# MotionControllerV1_1_EtherCAT.net
KiCad netlist of a schematic drawn in Altium Designer
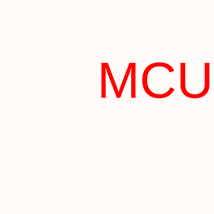
[diagram p0: MotionControllerV1.1_EtherCAT.SchDoc, top left]
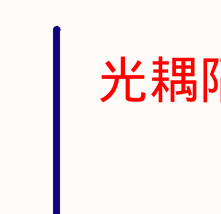
[diagram p1: MotionControllerV1.1_EtherCAT.SchDoc, top right]
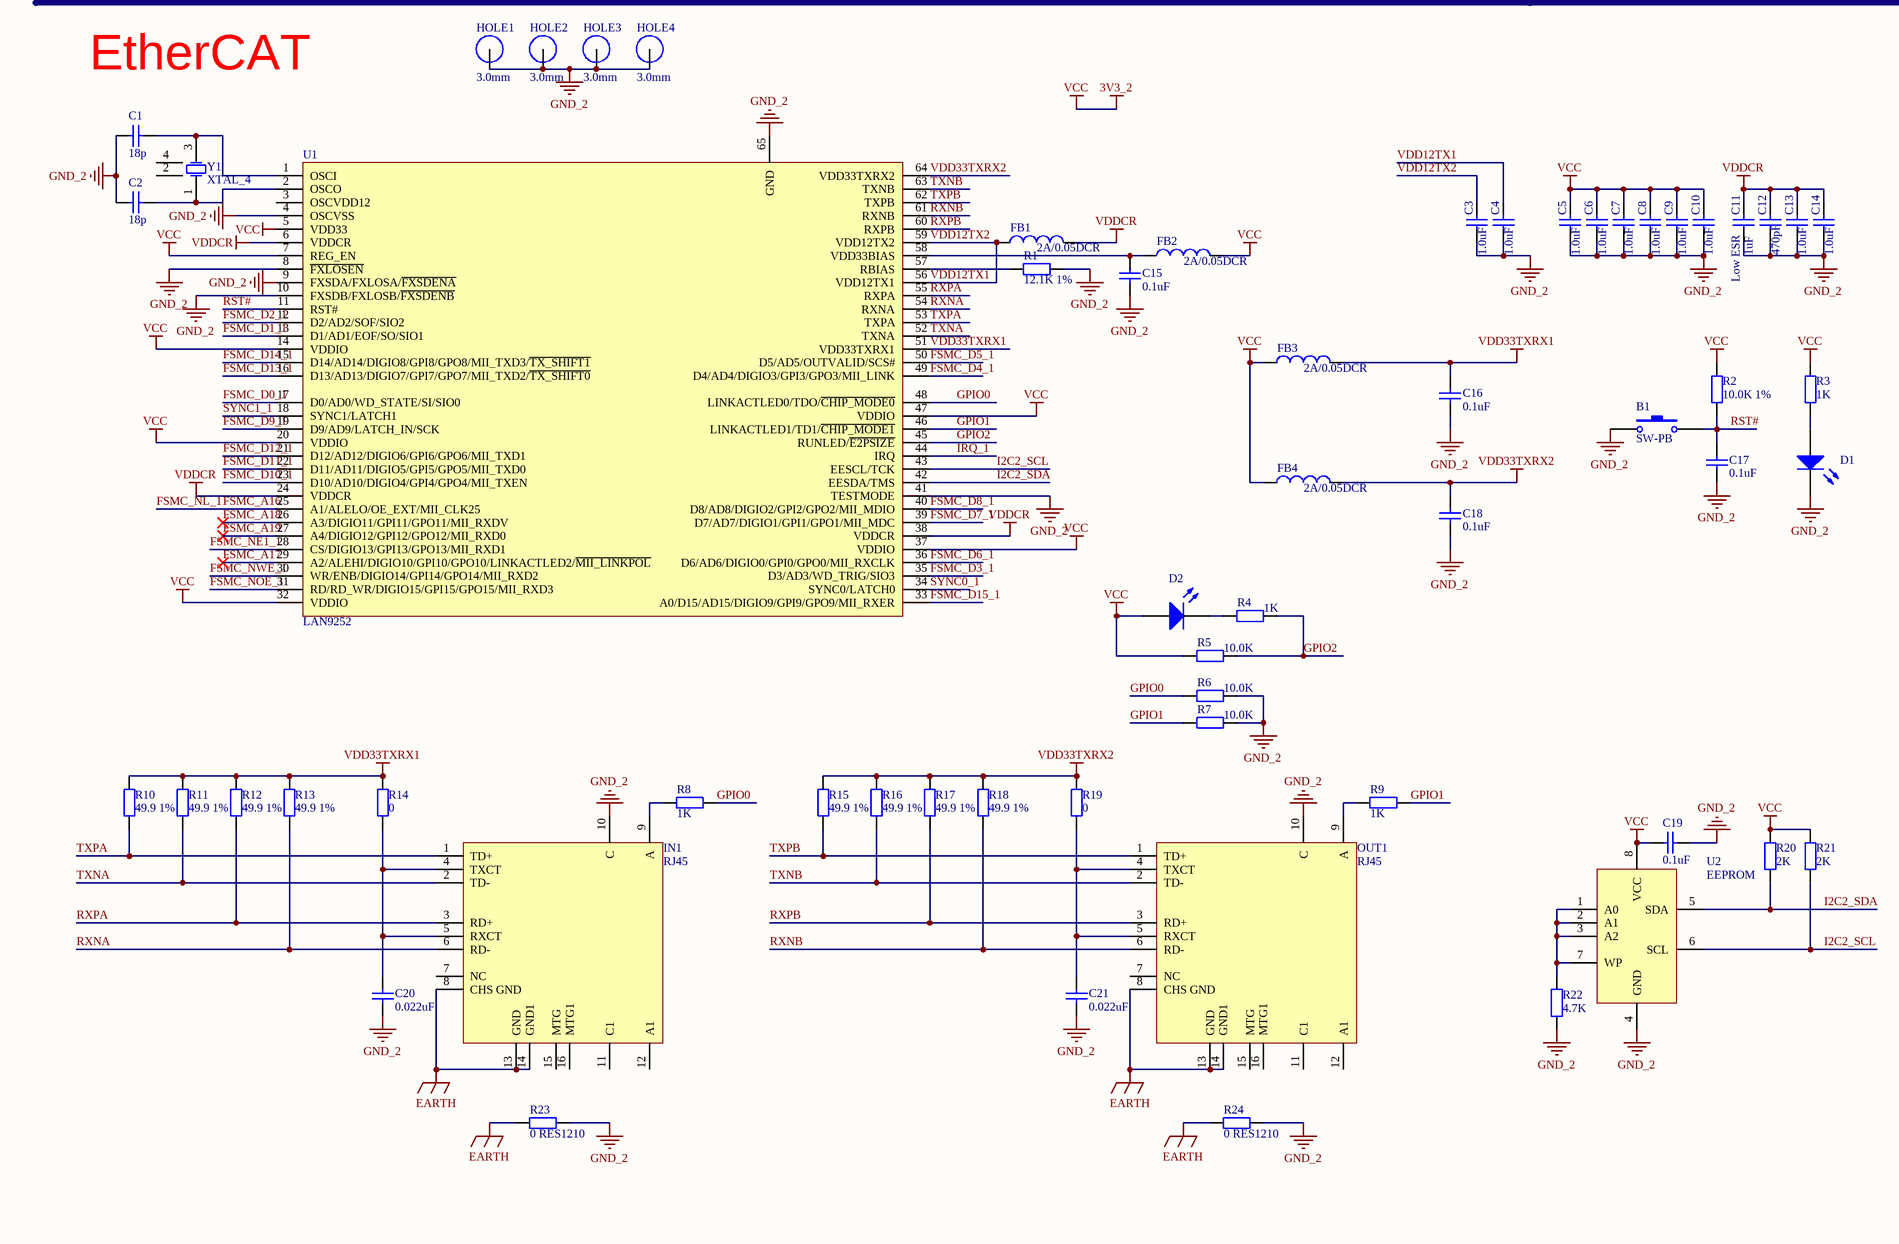
[diagram p2: MotionControllerV1.1_EtherCAT.SchDoc, bottom left]
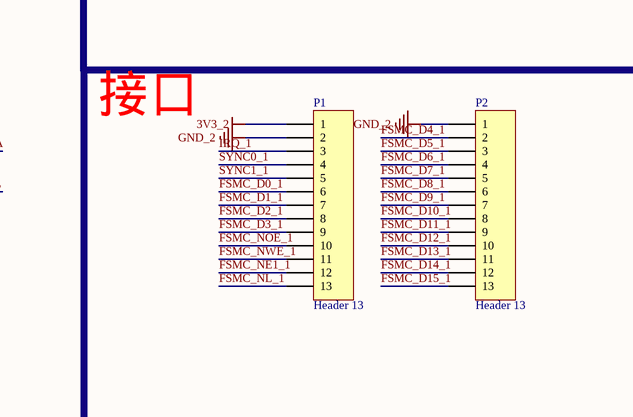
[diagram p3: MotionControllerV1.1_EtherCAT.SchDoc, bottom middle]
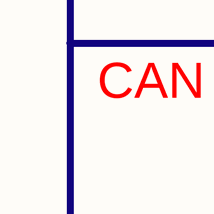
[diagram p4: MotionControllerV1.1_EtherCAT.SchDoc, bottom right]

(export (version "E")
  (design (tool "Eeschema 10.0.6"))
  (components
    (comp (ref "B1")
      (value "SW-PB")
      (footprint "TSW SMD-3*6*2.5")
      (description "Switch")
      (fields (field (name "PUBLISHER") "Altium Limited"))
      (libsource (lib "Miscellaneous Devices") (part "SW-PB"))
    )
    (comp (ref "C1")
      (value "18p")
      (footprint "0603_C")
      (description "Capacitor")
      (fields (field (name "Comment") "Cap") (field (name "PUBLISHER") "Altium Limited"))
      (libsource (lib "Miscellaneous Devices") (part "Cap"))
    )
    (comp (ref "C2")
      (value "18p")
      (footprint "0603_C")
      (description "Capacitor")
      (fields (field (name "Comment") "Cap") (field (name "PUBLISHER") "Altium Limited"))
      (libsource (lib "Miscellaneous Devices") (part "Cap"))
    )
    (comp (ref "C3")
      (value "1.0uF")
      (footprint "0603_C")
      (description "Capacitor")
      (fields (field (name "Comment") "Cap") (field (name "PUBLISHER") "Altium Limited"))
      (libsource (lib "Miscellaneous Devices") (part "Cap"))
    )
    (comp (ref "C4")
      (value "1.0uF")
      (footprint "0603_C")
      (description "Capacitor")
      (fields (field (name "Comment") "Cap") (field (name "PUBLISHER") "Altium Limited"))
      (libsource (lib "Miscellaneous Devices") (part "Cap"))
    )
    (comp (ref "C5")
      (value "1.0uF")
      (footprint "0603_C")
      (description "Capacitor")
      (fields (field (name "Comment") "Cap") (field (name "PUBLISHER") "Altium Limited"))
      (libsource (lib "Miscellaneous Devices") (part "Cap"))
    )
    (comp (ref "C6")
      (value "1.0uF")
      (footprint "0603_C")
      (description "Capacitor")
      (fields (field (name "Comment") "Cap") (field (name "PUBLISHER") "Altium Limited"))
      (libsource (lib "Miscellaneous Devices") (part "Cap"))
    )
    (comp (ref "C7")
      (value "1.0uF")
      (footprint "0603_C")
      (description "Capacitor")
      (fields (field (name "Comment") "Cap") (field (name "PUBLISHER") "Altium Limited"))
      (libsource (lib "Miscellaneous Devices") (part "Cap"))
    )
    (comp (ref "C8")
      (value "1.0uF")
      (footprint "0603_C")
      (description "Capacitor")
      (fields (field (name "Comment") "Cap") (field (name "PUBLISHER") "Altium Limited"))
      (libsource (lib "Miscellaneous Devices") (part "Cap"))
    )
    (comp (ref "C9")
      (value "1.0uF")
      (footprint "0603_C")
      (description "Capacitor")
      (fields (field (name "Comment") "Cap") (field (name "PUBLISHER") "Altium Limited"))
      (libsource (lib "Miscellaneous Devices") (part "Cap"))
    )
    (comp (ref "C10")
      (value "1.0uF")
      (footprint "0603_C")
      (description "Capacitor")
      (fields (field (name "Comment") "Cap") (field (name "PUBLISHER") "Altium Limited"))
      (libsource (lib "Miscellaneous Devices") (part "Cap"))
    )
    (comp (ref "C11")
      (value "1uF")
      (footprint "0603_C")
      (description "Capacitor")
      (fields (field (name "Comment") "Cap") (field (name "PUBLISHER") "Altium Limited"))
      (libsource (lib "Miscellaneous Devices") (part "Cap"))
    )
    (comp (ref "C12")
      (value "470pF")
      (footprint "0603_C")
      (description "Capacitor")
      (fields (field (name "Comment") "Cap") (field (name "PUBLISHER") "Altium Limited"))
      (libsource (lib "Miscellaneous Devices") (part "Cap"))
    )
    (comp (ref "C13")
      (value "1.0uF")
      (footprint "0603_C")
      (description "Capacitor")
      (fields (field (name "Comment") "Cap") (field (name "PUBLISHER") "Altium Limited"))
      (libsource (lib "Miscellaneous Devices") (part "Cap"))
    )
    (comp (ref "C14")
      (value "1.0uF")
      (footprint "0603_C")
      (description "Capacitor")
      (fields (field (name "Comment") "Cap") (field (name "PUBLISHER") "Altium Limited"))
      (libsource (lib "Miscellaneous Devices") (part "Cap"))
    )
    (comp (ref "C15")
      (value "0.1uF")
      (footprint "0603_C")
      (description "Capacitor")
      (fields (field (name "Comment") "Cap") (field (name "PUBLISHER") "Altium Limited"))
      (libsource (lib "Miscellaneous Devices") (part "Cap"))
    )
    (comp (ref "C16")
      (value "0.1uF")
      (footprint "0603_C")
      (description "Capacitor")
      (fields (field (name "Comment") "Cap") (field (name "PUBLISHER") "Altium Limited"))
      (libsource (lib "Miscellaneous Devices") (part "Cap"))
    )
    (comp (ref "C17")
      (value "0.1uF")
      (footprint "0603_C")
      (description "Capacitor")
      (fields (field (name "Comment") "Cap") (field (name "PUBLISHER") "Altium Limited"))
      (libsource (lib "Miscellaneous Devices") (part "Cap"))
    )
    (comp (ref "C18")
      (value "0.1uF")
      (footprint "0603_C")
      (description "Capacitor")
      (fields (field (name "Comment") "Cap") (field (name "PUBLISHER") "Altium Limited"))
      (libsource (lib "Miscellaneous Devices") (part "Cap"))
    )
    (comp (ref "C19")
      (value "0.1uF")
      (footprint "0603_C")
      (description "Capacitor")
      (fields (field (name "Comment") "Cap") (field (name "PUBLISHER") "Altium Limited"))
      (libsource (lib "Miscellaneous Devices") (part "Cap"))
    )
    (comp (ref "C20")
      (value "0.022uF")
      (footprint "0603_C")
      (description "Capacitor")
      (fields (field (name "Comment") "Cap") (field (name "PUBLISHER") "Altium Limited"))
      (libsource (lib "Miscellaneous Devices") (part "Cap"))
    )
    (comp (ref "C21")
      (value "0.022uF")
      (footprint "0603_C")
      (description "Capacitor")
      (fields (field (name "Comment") "Cap") (field (name "PUBLISHER") "Altium Limited"))
      (libsource (lib "Miscellaneous Devices") (part "Cap"))
    )
    (comp (ref "D1")
      (value "LED0")
      (footprint "0603_LED")
      (description "Typical INFRARED GaAs LED")
      (fields (field (name "PUBLISHER") "Altium Limited"))
      (libsource (lib "Miscellaneous Devices") (part "LED0"))
    )
    (comp (ref "D2")
      (value "LED0")
      (footprint "0603_LED")
      (description "Typical INFRARED GaAs LED")
      (fields (field (name "PUBLISHER") "Altium Limited"))
      (libsource (lib "Miscellaneous Devices") (part "LED0"))
    )
    (comp (ref "FB1")
      (value "2A/0.05DCR")
      (footprint "FU 0805")
      (description "Inductor")
      (fields (field (name "PUBLISHER") "Altium Limited"))
      (libsource (lib "Miscellaneous Devices") (part "Inductor"))
    )
    (comp (ref "FB2")
      (value "2A/0.05DCR")
      (footprint "FU 0805")
      (description "Inductor")
      (fields (field (name "PUBLISHER") "Altium Limited"))
      (libsource (lib "Miscellaneous Devices") (part "Inductor"))
    )
    (comp (ref "FB3")
      (value "2A/0.05DCR")
      (footprint "FU 0805")
      (description "Inductor")
      (fields (field (name "PUBLISHER") "Altium Limited"))
      (libsource (lib "Miscellaneous Devices") (part "Inductor"))
    )
    (comp (ref "FB4")
      (value "2A/0.05DCR")
      (footprint "FU 0805")
      (description "Inductor")
      (fields (field (name "PUBLISHER") "Altium Limited"))
      (libsource (lib "Miscellaneous Devices") (part "Inductor"))
    )
    (comp (ref "HOLE1")
      (value "3.0mm")
      (footprint "M2.5x6+6_L")
      (fields (field (name "Comment") "HOLE"))
      (libsource (lib "MYSchlib") (part "HOLE"))
    )
    (comp (ref "HOLE2")
      (value "3.0mm")
      (footprint "M2.5x6+6_L")
      (fields (field (name "Comment") "HOLE"))
      (libsource (lib "MYSchlib") (part "HOLE"))
    )
    (comp (ref "HOLE3")
      (value "3.0mm")
      (footprint "M2.5x6+6_L")
      (fields (field (name "Comment") "HOLE"))
      (libsource (lib "MYSchlib") (part "HOLE"))
    )
    (comp (ref "HOLE4")
      (value "3.0mm")
      (footprint "M2.5x6+6_L")
      (fields (field (name "Comment") "HOLE"))
      (libsource (lib "MYSchlib") (part "HOLE"))
    )
    (comp (ref "IN1") (value "RJ45") (footprint "RJ-45A12") (libsource (lib "Schlib1") (part "RJ45")))
    (comp (ref "OUT1") (value "RJ45") (footprint "RJ-45A12") (libsource (lib "Schlib1") (part "RJ45")))
    (comp (ref "P1")
      (value "Header 13")
      (footprint "HDR2.54-LI-13P")
      (description "Header, 13-Pin")
      (fields (field (name "PUBLISHER") "Altium Limited"))
      (libsource (lib "Miscellaneous Connectors") (part "Header 13"))
    )
    (comp (ref "P2")
      (value "Header 13")
      (footprint "HDR2.54-LI-13P")
      (description "Header, 13-Pin")
      (fields (field (name "PUBLISHER") "Altium Limited"))
      (libsource (lib "Miscellaneous Connectors") (part "Header 13"))
    )
    (comp (ref "R1")
      (value "12.1K 1%")
      (footprint "0603_R")
      (description "Resistor")
      (fields (field (name "Comment") "Res2") (field (name "PUBLISHER") "Altium Limited"))
      (libsource (lib "Miscellaneous Devices") (part "Res2"))
    )
    (comp (ref "R2")
      (value "10.0K 1%")
      (footprint "0603_R")
      (description "Resistor")
      (fields (field (name "Comment") "Res2") (field (name "PUBLISHER") "Altium Limited"))
      (libsource (lib "") (part "Res2_1"))
    )
    (comp (ref "R3")
      (value "1K")
      (footprint "0603_R")
      (description "Resistor")
      (fields (field (name "Comment") "Res2") (field (name "PUBLISHER") "Altium Limited"))
      (libsource (lib "") (part "Res2_1"))
    )
    (comp (ref "R4")
      (value "1K")
      (footprint "0603_R")
      (description "Resistor")
      (fields (field (name "Comment") "Res2") (field (name "PUBLISHER") "Altium Limited"))
      (libsource (lib "Miscellaneous Devices") (part "Res2"))
    )
    (comp (ref "R5")
      (value "10.0K")
      (footprint "0603_R")
      (description "Resistor")
      (fields (field (name "Comment") "Res2") (field (name "PUBLISHER") "Altium Limited"))
      (libsource (lib "Miscellaneous Devices") (part "Res2"))
    )
    (comp (ref "R6")
      (value "10.0K")
      (footprint "0603_R")
      (description "Resistor")
      (fields (field (name "Comment") "Res2") (field (name "PUBLISHER") "Altium Limited"))
      (libsource (lib "Miscellaneous Devices") (part "Res2"))
    )
    (comp (ref "R7")
      (value "10.0K")
      (footprint "0603_R")
      (description "Resistor")
      (fields (field (name "Comment") "Res2") (field (name "PUBLISHER") "Altium Limited"))
      (libsource (lib "Miscellaneous Devices") (part "Res2"))
    )
    (comp (ref "R8")
      (value "1K")
      (footprint "0603_R")
      (description "Resistor")
      (fields (field (name "Comment") "Res2") (field (name "PUBLISHER") "Altium Limited"))
      (libsource (lib "Miscellaneous Devices") (part "Res2"))
    )
    (comp (ref "R9")
      (value "1K")
      (footprint "0603_R")
      (description "Resistor")
      (fields (field (name "Comment") "Res2") (field (name "PUBLISHER") "Altium Limited"))
      (libsource (lib "Miscellaneous Devices") (part "Res2"))
    )
    (comp (ref "R10")
      (value "49.9 1%")
      (footprint "0603_R")
      (description "Resistor")
      (fields (field (name "Comment") "Res2") (field (name "PUBLISHER") "Altium Limited"))
      (libsource (lib "") (part "Res2_2"))
    )
    (comp (ref "R11")
      (value "49.9 1%")
      (footprint "0603_R")
      (description "Resistor")
      (fields (field (name "Comment") "Res2") (field (name "PUBLISHER") "Altium Limited"))
      (libsource (lib "") (part "Res2_2"))
    )
    (comp (ref "R12")
      (value "49.9 1%")
      (footprint "0603_R")
      (description "Resistor")
      (fields (field (name "Comment") "Res2") (field (name "PUBLISHER") "Altium Limited"))
      (libsource (lib "") (part "Res2_2"))
    )
    (comp (ref "R13")
      (value "49.9 1%")
      (footprint "0603_R")
      (description "Resistor")
      (fields (field (name "Comment") "Res2") (field (name "PUBLISHER") "Altium Limited"))
      (libsource (lib "") (part "Res2_2"))
    )
    (comp (ref "R14")
      (value "0")
      (footprint "0603_R")
      (description "Resistor")
      (fields (field (name "Comment") "Res2") (field (name "PUBLISHER") "Altium Limited"))
      (libsource (lib "") (part "Res2_2"))
    )
    (comp (ref "R15")
      (value "49.9 1%")
      (footprint "0603_R")
      (description "Resistor")
      (fields (field (name "Comment") "Res2") (field (name "PUBLISHER") "Altium Limited"))
      (libsource (lib "") (part "Res2_2"))
    )
    (comp (ref "R16")
      (value "49.9 1%")
      (footprint "0603_R")
      (description "Resistor")
      (fields (field (name "Comment") "Res2") (field (name "PUBLISHER") "Altium Limited"))
      (libsource (lib "") (part "Res2_2"))
    )
    (comp (ref "R17")
      (value "49.9 1%")
      (footprint "0603_R")
      (description "Resistor")
      (fields (field (name "Comment") "Res2") (field (name "PUBLISHER") "Altium Limited"))
      (libsource (lib "") (part "Res2_2"))
    )
    (comp (ref "R18")
      (value "49.9 1%")
      (footprint "0603_R")
      (description "Resistor")
      (fields (field (name "Comment") "Res2") (field (name "PUBLISHER") "Altium Limited"))
      (libsource (lib "") (part "Res2_2"))
    )
    (comp (ref "R19")
      (value "0")
      (footprint "0603_R")
      (description "Resistor")
      (fields (field (name "Comment") "Res2") (field (name "PUBLISHER") "Altium Limited"))
      (libsource (lib "") (part "Res2_2"))
    )
    (comp (ref "R20")
      (value "2K")
      (footprint "0603_R")
      (description "Resistor")
      (fields (field (name "Comment") "Res2") (field (name "PUBLISHER") "Altium Limited"))
      (libsource (lib "") (part "Res2_1"))
    )
    (comp (ref "R21")
      (value "2K")
      (footprint "0603_R")
      (description "Resistor")
      (fields (field (name "Comment") "Res2") (field (name "PUBLISHER") "Altium Limited"))
      (libsource (lib "") (part "Res2_1"))
    )
    (comp (ref "R22")
      (value "4.7K")
      (footprint "0603_R")
      (description "Resistor")
      (fields (field (name "Comment") "Res2") (field (name "PUBLISHER") "Altium Limited"))
      (libsource (lib "") (part "Res2_1"))
    )
    (comp (ref "R23")
      (value "0 RES1210")
      (footprint "0603_R")
      (description "Resistor")
      (fields (field (name "Comment") "Res2") (field (name "PUBLISHER") "Altium Limited"))
      (libsource (lib "Miscellaneous Devices") (part "Res2"))
    )
    (comp (ref "R24")
      (value "0 RES1210")
      (footprint "0603_R")
      (description "Resistor")
      (fields (field (name "Comment") "Res2") (field (name "PUBLISHER") "Altium Limited"))
      (libsource (lib "Miscellaneous Devices") (part "Res2"))
    )
    (comp (ref "U1") (value "LAN9252") (footprint "QFN64") (libsource (lib "Schlib1") (part "LAN9252")))
    (comp (ref "U2") (value "EEPROM") (footprint "SOP8") (libsource (lib "Schlib1") (part "EEPROM")))
    (comp (ref "Y1")
      (value "XTAL_4")
      (footprint "OSC 3225-4P")
      (description "Crystal Oscillator")
      (fields (field (name "PUBLISHER") "Altium Limited"))
      (libsource (lib "MYSchlib") (part "XTAL_4"))
    )
  )
  (nets
    (net (code "1") (name "/FSMC_A16") (class "Default")
      (node (ref "P1") (pin "13") (pinfunction "13_13") (pintype "passive"))
      (node (ref "U1") (pin "25") (pinfunction "A1/ALELO/OE_EXT/MII_CLK25_25") (pintype "passive"))
    )
    (net (code "2") (name "/FSMC_A17") (class "Default")
      (node (ref "U1") (pin "29") (pinfunction "A2/ALEHI/DIGIO10/GPI10/GPO10/LINKACTLED2/~{MII_LINKPOL}_29") (pintype "passive+no_connect"))
    )
    (net (code "3") (name "/FSMC_A18") (class "Default")
      (node (ref "U1") (pin "26") (pinfunction "A3/DIGIO11/GPI11/GPO11/MII_RXDV_26") (pintype "passive+no_connect"))
    )
    (net (code "4") (name "/FSMC_A19") (class "Default")
      (node (ref "U1") (pin "27") (pinfunction "A4/DIGIO12/GPI12/GPO12/MII_RXD0_27") (pintype "passive+no_connect"))
    )
    (net (code "5") (name "/FSMC_D0_1") (class "Default")
      (node (ref "P1") (pin "6") (pinfunction "6_6") (pintype "passive"))
      (node (ref "U1") (pin "17") (pinfunction "D0/AD0/WD_STATE/SI/SIO0_17") (pintype "passive"))
    )
    (net (code "6") (name "/FSMC_D1_1") (class "Default")
      (node (ref "P1") (pin "7") (pinfunction "7_7") (pintype "passive"))
      (node (ref "U1") (pin "13") (pinfunction "D1/AD1/EOF/SO/SIO1_13") (pintype "passive"))
    )
    (net (code "7") (name "/FSMC_D2_1") (class "Default")
      (node (ref "P1") (pin "8") (pinfunction "8_8") (pintype "passive"))
      (node (ref "U1") (pin "12") (pinfunction "D2/AD2/SOF/SIO2_12") (pintype "passive"))
    )
    (net (code "8") (name "/FSMC_D3_1") (class "Default")
      (node (ref "P1") (pin "9") (pinfunction "9_9") (pintype "passive"))
      (node (ref "U1") (pin "35") (pinfunction "D3/AD3/WD_TRIG/SIO3_35") (pintype "passive"))
    )
    (net (code "9") (name "/FSMC_D4_1") (class "Default")
      (node (ref "P2") (pin "2") (pinfunction "2_2") (pintype "passive"))
      (node (ref "U1") (pin "49") (pinfunction "D4/AD4/DIGIO3/GPI3/GPO3/MII_LINK_49") (pintype "passive"))
    )
    (net (code "10") (name "/FSMC_D5_1") (class "Default")
      (node (ref "P2") (pin "3") (pinfunction "3_3") (pintype "passive"))
      (node (ref "U1") (pin "50") (pinfunction "D5/AD5/OUTVALID/SCS#_50") (pintype "passive"))
    )
    (net (code "11") (name "/FSMC_D6_1") (class "Default")
      (node (ref "P2") (pin "4") (pinfunction "4_4") (pintype "passive"))
      (node (ref "U1") (pin "36") (pinfunction "D6/AD6/DIGIO0/GPI0/GPO0/MII_RXCLK_36") (pintype "passive"))
    )
    (net (code "12") (name "/FSMC_D7_1") (class "Default")
      (node (ref "P2") (pin "5") (pinfunction "5_5") (pintype "passive"))
      (node (ref "U1") (pin "39") (pinfunction "D7/AD7/DIGIO1/GPI1/GPO1/MII_MDC_39") (pintype "passive"))
    )
    (net (code "13") (name "/FSMC_D8_1") (class "Default")
      (node (ref "P2") (pin "6") (pinfunction "6_6") (pintype "passive"))
      (node (ref "U1") (pin "40") (pinfunction "D8/AD8/DIGIO2/GPI2/GPO2/MII_MDIO_40") (pintype "passive"))
    )
    (net (code "14") (name "/FSMC_D9_1") (class "Default")
      (node (ref "P2") (pin "7") (pinfunction "7_7") (pintype "passive"))
      (node (ref "U1") (pin "19") (pinfunction "D9/AD9/LATCH_IN/SCK_19") (pintype "passive"))
    )
    (net (code "15") (name "/FSMC_D10_1") (class "Default")
      (node (ref "P2") (pin "8") (pinfunction "8_8") (pintype "passive"))
      (node (ref "U1") (pin "23") (pinfunction "D10/AD10/DIGIO4/GPI4/GPO4/MII_TXEN_23") (pintype "passive"))
    )
    (net (code "16") (name "/FSMC_D11_1") (class "Default")
      (node (ref "P2") (pin "9") (pinfunction "9_9") (pintype "passive"))
      (node (ref "U1") (pin "22") (pinfunction "D11/AD11/DIGIO5/GPI5/GPO5/MII_TXD0_22") (pintype "passive"))
    )
    (net (code "17") (name "/FSMC_D12_1") (class "Default")
      (node (ref "P2") (pin "10") (pinfunction "10_10") (pintype "passive"))
      (node (ref "U1") (pin "21") (pinfunction "D12/AD12/DIGIO6/GPI6/GPO6/MII_TXD1_21") (pintype "passive"))
    )
    (net (code "18") (name "/FSMC_D13_1") (class "Default")
      (node (ref "P2") (pin "11") (pinfunction "11_11") (pintype "passive"))
      (node (ref "U1") (pin "16") (pinfunction "D13/AD13/DIGIO7/GPI7/GPO7/MII_TXD2/~{TX_SHIFT0}_16") (pintype "passive"))
    )
    (net (code "19") (name "/FSMC_D14_1") (class "Default")
      (node (ref "P2") (pin "12") (pinfunction "12_12") (pintype "passive"))
      (node (ref "U1") (pin "15") (pinfunction "D14/AD14/DIGIO8/GPI8/GPO8/MII_TXD3/~{TX_SHIFT1}_15") (pintype "passive"))
    )
    (net (code "20") (name "/FSMC_D15_1") (class "Default")
      (node (ref "P2") (pin "13") (pinfunction "13_13") (pintype "passive"))
      (node (ref "U1") (pin "33") (pinfunction "A0/D15/AD15/DIGIO9/GPI9/GPO9/MII_RXER_33") (pintype "passive"))
    )
    (net (code "21") (name "/FSMC_NE1_1") (class "Default")
      (node (ref "P1") (pin "12") (pinfunction "12_12") (pintype "passive"))
      (node (ref "U1") (pin "28") (pinfunction "CS/DIGIO13/GPI13/GPO13/MII_RXD1_28") (pintype "passive"))
    )
    (net (code "22") (name "/FSMC_NOE_1") (class "Default")
      (node (ref "P1") (pin "10") (pinfunction "10_10") (pintype "passive"))
      (node (ref "U1") (pin "31") (pinfunction "RD/RD_WR/DIGIO15/GPI15/GPO15/MII_RXD3_31") (pintype "passive"))
    )
    (net (code "23") (name "/FSMC_NWE_1") (class "Default")
      (node (ref "P1") (pin "11") (pinfunction "11_11") (pintype "passive"))
      (node (ref "U1") (pin "30") (pinfunction "WR/ENB/DIGIO14/GPI14/GPO14/MII_RXD2_30") (pintype "passive"))
    )
    (net (code "24") (name "/GPIO0") (class "Default")
      (node (ref "R6") (pin "2") (pinfunction "2_2") (pintype "passive"))
      (node (ref "R8") (pin "1") (pinfunction "1_1") (pintype "passive"))
      (node (ref "U1") (pin "48") (pinfunction "LINKACTLED0/TDO/~{CHIP_MODE0}_48") (pintype "passive"))
    )
    (net (code "25") (name "/GPIO1") (class "Default")
      (node (ref "R7") (pin "2") (pinfunction "2_2") (pintype "passive"))
      (node (ref "R9") (pin "1") (pinfunction "1_1") (pintype "passive"))
      (node (ref "U1") (pin "46") (pinfunction "LINKACTLED1/TD1/~{CHIP_MODE1}_46") (pintype "passive"))
    )
    (net (code "26") (name "/GPIO2") (class "Default")
      (node (ref "R4") (pin "1") (pinfunction "1_1") (pintype "passive"))
      (node (ref "R5") (pin "1") (pinfunction "1_1") (pintype "passive"))
      (node (ref "U1") (pin "45") (pinfunction "RUNLED/~{E2PSIZE}_45") (pintype "passive"))
    )
    (net (code "27") (name "/I2C2_SCL") (class "Default")
      (node (ref "R21") (pin "2") (pinfunction "2_2") (pintype "passive"))
      (node (ref "U1") (pin "43") (pinfunction "EESCL/TCK_43") (pintype "passive"))
      (node (ref "U2") (pin "6") (pinfunction "SCL_6") (pintype "passive"))
    )
    (net (code "28") (name "/I2C2_SDA") (class "Default")
      (node (ref "R20") (pin "2") (pinfunction "2_2") (pintype "passive"))
      (node (ref "U1") (pin "42") (pinfunction "EESDA/TMS_42") (pintype "passive"))
      (node (ref "U2") (pin "5") (pinfunction "SDA_5") (pintype "passive"))
    )
    (net (code "29") (name "/IRQ_1") (class "Default")
      (node (ref "P1") (pin "3") (pinfunction "3_3") (pintype "passive"))
      (node (ref "U1") (pin "44") (pinfunction "IRQ_44") (pintype "passive"))
    )
    (net (code "30") (name "/RST#") (class "Default")
      (node (ref "B1") (pin "2") (pinfunction "2_2") (pintype "passive"))
      (node (ref "C17") (pin "1") (pinfunction "1_1") (pintype "passive"))
      (node (ref "R2") (pin "2") (pinfunction "2_2") (pintype "passive"))
      (node (ref "U1") (pin "11") (pinfunction "RST#_11") (pintype "passive"))
    )
    (net (code "31") (name "/RXNA") (class "Default")
      (node (ref "IN1") (pin "6") (pinfunction "RD-_6") (pintype "passive"))
      (node (ref "R13") (pin "1") (pinfunction "1_1") (pintype "passive"))
      (node (ref "U1") (pin "54") (pinfunction "RXNA_54") (pintype "passive"))
    )
    (net (code "32") (name "/RXNB") (class "Default")
      (node (ref "OUT1") (pin "6") (pinfunction "RD-_6") (pintype "passive"))
      (node (ref "R18") (pin "1") (pinfunction "1_1") (pintype "passive"))
      (node (ref "U1") (pin "61") (pinfunction "RXNB_61") (pintype "passive"))
    )
    (net (code "33") (name "/RXPA") (class "Default")
      (node (ref "IN1") (pin "3") (pinfunction "RD+_3") (pintype "passive"))
      (node (ref "R12") (pin "1") (pinfunction "1_1") (pintype "passive"))
      (node (ref "U1") (pin "55") (pinfunction "RXPA_55") (pintype "passive"))
    )
    (net (code "34") (name "/RXPB") (class "Default")
      (node (ref "OUT1") (pin "3") (pinfunction "RD+_3") (pintype "passive"))
      (node (ref "R17") (pin "1") (pinfunction "1_1") (pintype "passive"))
      (node (ref "U1") (pin "60") (pinfunction "RXPB_60") (pintype "passive"))
    )
    (net (code "35") (name "/SYNC0_1") (class "Default")
      (node (ref "P1") (pin "4") (pinfunction "4_4") (pintype "passive"))
      (node (ref "U1") (pin "34") (pinfunction "SYNC0/LATCH0_34") (pintype "passive"))
    )
    (net (code "36") (name "/SYNC1_1") (class "Default")
      (node (ref "P1") (pin "5") (pinfunction "5_5") (pintype "passive"))
      (node (ref "U1") (pin "18") (pinfunction "SYNC1/LATCH1_18") (pintype "passive"))
    )
    (net (code "37") (name "/TXNA") (class "Default")
      (node (ref "IN1") (pin "2") (pinfunction "TD-_2") (pintype "passive"))
      (node (ref "R11") (pin "1") (pinfunction "1_1") (pintype "passive"))
      (node (ref "U1") (pin "52") (pinfunction "TXNA_52") (pintype "passive"))
    )
    (net (code "38") (name "/TXNB") (class "Default")
      (node (ref "OUT1") (pin "2") (pinfunction "TD-_2") (pintype "passive"))
      (node (ref "R16") (pin "1") (pinfunction "1_1") (pintype "passive"))
      (node (ref "U1") (pin "63") (pinfunction "TXNB_63") (pintype "passive"))
    )
    (net (code "39") (name "/TXPA") (class "Default")
      (node (ref "IN1") (pin "1") (pinfunction "TD+_1") (pintype "passive"))
      (node (ref "R10") (pin "1") (pinfunction "1_1") (pintype "passive"))
      (node (ref "U1") (pin "53") (pinfunction "TXPA_53") (pintype "passive"))
    )
    (net (code "40") (name "/TXPB") (class "Default")
      (node (ref "OUT1") (pin "1") (pinfunction "TD+_1") (pintype "passive"))
      (node (ref "R15") (pin "1") (pinfunction "1_1") (pintype "passive"))
      (node (ref "U1") (pin "62") (pinfunction "TXPB_62") (pintype "passive"))
    )
    (net (code "41") (name "/VDD12TX1") (class "Default")
      (node (ref "C3") (pin "2") (pinfunction "2_2") (pintype "passive"))
      (node (ref "C4") (pin "2") (pinfunction "2_2") (pintype "passive"))
      (node (ref "FB1") (pin "1") (pinfunction "1_1") (pintype "passive"))
      (node (ref "U1") (pin "56") (pinfunction "VDD12TX1_56") (pintype "passive"))
      (node (ref "U1") (pin "59") (pinfunction "VDD12TX2_59") (pintype "passive"))
    )
    (net (code "42") (name "3V3_2") (class "Default")
      (node (ref "C10") (pin "2") (pinfunction "2_2") (pintype "passive"))
      (node (ref "C19") (pin "1") (pinfunction "1_1") (pintype "passive"))
      (node (ref "C5") (pin "2") (pinfunction "2_2") (pintype "passive"))
      (node (ref "C6") (pin "2") (pinfunction "2_2") (pintype "passive"))
      (node (ref "C7") (pin "2") (pinfunction "2_2") (pintype "passive"))
      (node (ref "C8") (pin "2") (pinfunction "2_2") (pintype "passive"))
      (node (ref "C9") (pin "2") (pinfunction "2_2") (pintype "passive"))
      (node (ref "D2") (pin "1") (pinfunction "A_1") (pintype "passive"))
      (node (ref "FB2") (pin "2") (pinfunction "2_2") (pintype "passive"))
      (node (ref "FB3") (pin "1") (pinfunction "1_1") (pintype "passive"))
      (node (ref "FB4") (pin "1") (pinfunction "1_1") (pintype "passive"))
      (node (ref "P1") (pin "1") (pinfunction "1_1") (pintype "passive"))
      (node (ref "R2") (pin "1") (pinfunction "1_1") (pintype "passive"))
      (node (ref "R20") (pin "1") (pinfunction "1_1") (pintype "passive"))
      (node (ref "R21") (pin "1") (pinfunction "1_1") (pintype "passive"))
      (node (ref "R3") (pin "1") (pinfunction "1_1") (pintype "passive"))
      (node (ref "R5") (pin "2") (pinfunction "2_2") (pintype "passive"))
      (node (ref "U1") (pin "14") (pinfunction "VDDIO_14") (pintype "passive"))
      (node (ref "U1") (pin "20") (pinfunction "VDDIO_20") (pintype "passive"))
      (node (ref "U1") (pin "32") (pinfunction "VDDIO_32") (pintype "passive"))
      (node (ref "U1") (pin "37") (pinfunction "VDDIO_37") (pintype "passive"))
      (node (ref "U1") (pin "47") (pinfunction "VDDIO_47") (pintype "passive"))
      (node (ref "U1") (pin "5") (pinfunction "VDD33_5") (pintype "passive"))
      (node (ref "U1") (pin "7") (pinfunction "REG_EN_7") (pintype "passive"))
      (node (ref "U2") (pin "8") (pinfunction "VCC_8") (pintype "passive"))
    )
    (net (code "43") (name "EARTH") (class "Default")
      (node (ref "IN1") (pin "13") (pinfunction "GND_13") (pintype "passive"))
      (node (ref "IN1") (pin "14") (pinfunction "GND1_14") (pintype "passive"))
      (node (ref "IN1") (pin "8") (pinfunction "CHS_GND_8") (pintype "passive"))
      (node (ref "OUT1") (pin "13") (pinfunction "GND_13") (pintype "passive"))
      (node (ref "OUT1") (pin "14") (pinfunction "GND1_14") (pintype "passive"))
      (node (ref "OUT1") (pin "8") (pinfunction "CHS_GND_8") (pintype "passive"))
      (node (ref "R23") (pin "2") (pinfunction "2_2") (pintype "passive"))
      (node (ref "R24") (pin "2") (pinfunction "2_2") (pintype "passive"))
    )
    (net (code "44") (name "GND_2") (class "Default")
      (node (ref "B1") (pin "1") (pinfunction "1_1") (pintype "passive"))
      (node (ref "C1") (pin "2") (pinfunction "2_2") (pintype "passive"))
      (node (ref "C10") (pin "1") (pinfunction "1_1") (pintype "passive"))
      (node (ref "C11") (pin "1") (pinfunction "1_1") (pintype "passive"))
      (node (ref "C12") (pin "1") (pinfunction "1_1") (pintype "passive"))
      (node (ref "C13") (pin "1") (pinfunction "1_1") (pintype "passive"))
      (node (ref "C14") (pin "1") (pinfunction "1_1") (pintype "passive"))
      (node (ref "C15") (pin "2") (pinfunction "2_2") (pintype "passive"))
      (node (ref "C16") (pin "2") (pinfunction "2_2") (pintype "passive"))
      (node (ref "C17") (pin "2") (pinfunction "2_2") (pintype "passive"))
      (node (ref "C18") (pin "2") (pinfunction "2_2") (pintype "passive"))
      (node (ref "C19") (pin "2") (pinfunction "2_2") (pintype "passive"))
      (node (ref "C2") (pin "2") (pinfunction "2_2") (pintype "passive"))
      (node (ref "C20") (pin "2") (pinfunction "2_2") (pintype "passive"))
      (node (ref "C21") (pin "2") (pinfunction "2_2") (pintype "passive"))
      (node (ref "C3") (pin "1") (pinfunction "1_1") (pintype "passive"))
      (node (ref "C4") (pin "1") (pinfunction "1_1") (pintype "passive"))
      (node (ref "C5") (pin "1") (pinfunction "1_1") (pintype "passive"))
      (node (ref "C6") (pin "1") (pinfunction "1_1") (pintype "passive"))
      (node (ref "C7") (pin "1") (pinfunction "1_1") (pintype "passive"))
      (node (ref "C8") (pin "1") (pinfunction "1_1") (pintype "passive"))
      (node (ref "C9") (pin "1") (pinfunction "1_1") (pintype "passive"))
      (node (ref "D1") (pin "2") (pinfunction "K_2") (pintype "passive"))
      (node (ref "HOLE1") (pin "1") (pintype "passive"))
      (node (ref "HOLE2") (pin "1") (pintype "passive"))
      (node (ref "HOLE3") (pin "1") (pintype "passive"))
      (node (ref "HOLE4") (pin "1") (pintype "passive"))
      (node (ref "IN1") (pin "10") (pinfunction "C_10") (pintype "passive"))
      (node (ref "OUT1") (pin "10") (pinfunction "C_10") (pintype "passive"))
      (node (ref "P1") (pin "2") (pinfunction "2_2") (pintype "passive"))
      (node (ref "P2") (pin "1") (pinfunction "1_1") (pintype "passive"))
      (node (ref "R1") (pin "1") (pinfunction "1_1") (pintype "passive"))
      (node (ref "R22") (pin "2") (pinfunction "2_2") (pintype "passive"))
      (node (ref "R23") (pin "1") (pinfunction "1_1") (pintype "passive"))
      (node (ref "R24") (pin "1") (pinfunction "1_1") (pintype "passive"))
      (node (ref "R6") (pin "1") (pinfunction "1_1") (pintype "passive"))
      (node (ref "R7") (pin "1") (pinfunction "1_1") (pintype "passive"))
      (node (ref "U1") (pin "10") (pinfunction "FXSDB/FXLOSB/~{FXSDENB}_10") (pintype "passive"))
      (node (ref "U1") (pin "4") (pinfunction "OSCVSS_4") (pintype "passive"))
      (node (ref "U1") (pin "41") (pinfunction "TESTMODE_41") (pintype "passive"))
      (node (ref "U1") (pin "65") (pinfunction "GND_65") (pintype "passive"))
      (node (ref "U1") (pin "8") (pinfunction "~{FXLOSEN}_8") (pintype "passive"))
      (node (ref "U1") (pin "9") (pinfunction "FXSDA/FXLOSA/~{FXSDENA}_9") (pintype "passive"))
      (node (ref "U2") (pin "4") (pinfunction "GND_4") (pintype "passive"))
    )
    (net (code "45") (name "Net-(D1-A)") (class "Default")
      (node (ref "D1") (pin "1") (pinfunction "A_1") (pintype "passive"))
      (node (ref "R3") (pin "2") (pinfunction "2_2") (pintype "passive"))
    )
    (net (code "46") (name "Net-(D2-K)") (class "Default")
      (node (ref "D2") (pin "2") (pinfunction "K_2") (pintype "passive"))
      (node (ref "R4") (pin "2") (pinfunction "2_2") (pintype "passive"))
    )
    (net (code "47") (name "Net-(IN1-A)") (class "Default")
      (node (ref "IN1") (pin "9") (pinfunction "A_9") (pintype "passive"))
      (node (ref "R8") (pin "2") (pinfunction "2_2") (pintype "passive"))
    )
    (net (code "48") (name "Net-(IN1-RXCT)") (class "Default")
      (node (ref "C20") (pin "1") (pinfunction "1_1") (pintype "passive"))
      (node (ref "IN1") (pin "4") (pinfunction "TXCT_4") (pintype "passive"))
      (node (ref "IN1") (pin "5") (pinfunction "RXCT_5") (pintype "passive"))
      (node (ref "R14") (pin "1") (pinfunction "1_1") (pintype "passive"))
    )
    (net (code "49") (name "Net-(OUT1-A)") (class "Default")
      (node (ref "OUT1") (pin "9") (pinfunction "A_9") (pintype "passive"))
      (node (ref "R9") (pin "2") (pinfunction "2_2") (pintype "passive"))
    )
    (net (code "50") (name "Net-(OUT1-RXCT)") (class "Default")
      (node (ref "C21") (pin "1") (pinfunction "1_1") (pintype "passive"))
      (node (ref "OUT1") (pin "4") (pinfunction "TXCT_4") (pintype "passive"))
      (node (ref "OUT1") (pin "5") (pinfunction "RXCT_5") (pintype "passive"))
      (node (ref "R19") (pin "1") (pinfunction "1_1") (pintype "passive"))
    )
    (net (code "51") (name "Net-(U1-OSCI)") (class "Default")
      (node (ref "C1") (pin "1") (pinfunction "1_1") (pintype "passive"))
      (node (ref "U1") (pin "1") (pinfunction "OSCI_1") (pintype "passive"))
      (node (ref "Y1") (pin "3") (pinfunction "OSC2_3") (pintype "passive"))
    )
    (net (code "52") (name "Net-(U1-OSCO)") (class "Default")
      (node (ref "C2") (pin "1") (pinfunction "1_1") (pintype "passive"))
      (node (ref "U1") (pin "2") (pinfunction "OSCO_2") (pintype "passive"))
      (node (ref "Y1") (pin "1") (pinfunction "OSC1_1") (pintype "passive"))
    )
    (net (code "53") (name "Net-(U1-RBIAS)") (class "Default")
      (node (ref "R1") (pin "2") (pinfunction "2_2") (pintype "passive"))
      (node (ref "U1") (pin "57") (pinfunction "RBIAS_57") (pintype "passive"))
    )
    (net (code "54") (name "Net-(U1-VDD33BIAS)") (class "Default")
      (node (ref "C15") (pin "1") (pinfunction "1_1") (pintype "passive"))
      (node (ref "FB2") (pin "1") (pinfunction "1_1") (pintype "passive"))
      (node (ref "U1") (pin "58") (pinfunction "VDD33BIAS_58") (pintype "passive"))
    )
    (net (code "55") (name "Net-(U2-A0)") (class "Default")
      (node (ref "R22") (pin "1") (pinfunction "1_1") (pintype "passive"))
      (node (ref "U2") (pin "1") (pinfunction "A0_1") (pintype "passive"))
      (node (ref "U2") (pin "2") (pinfunction "A1_2") (pintype "passive"))
      (node (ref "U2") (pin "3") (pinfunction "A2_3") (pintype "passive"))
      (node (ref "U2") (pin "7") (pinfunction "WP_7") (pintype "passive"))
    )
    (net (code "56") (name "VDD33TXRX1") (class "Default")
      (node (ref "C16") (pin "1") (pinfunction "1_1") (pintype "passive"))
      (node (ref "FB3") (pin "2") (pinfunction "2_2") (pintype "passive"))
      (node (ref "R10") (pin "2") (pinfunction "2_2") (pintype "passive"))
      (node (ref "R11") (pin "2") (pinfunction "2_2") (pintype "passive"))
      (node (ref "R12") (pin "2") (pinfunction "2_2") (pintype "passive"))
      (node (ref "R13") (pin "2") (pinfunction "2_2") (pintype "passive"))
      (node (ref "R14") (pin "2") (pinfunction "2_2") (pintype "passive"))
      (node (ref "U1") (pin "51") (pinfunction "VDD33TXRX1_51") (pintype "passive"))
    )
    (net (code "57") (name "VDD33TXRX2") (class "Default")
      (node (ref "C18") (pin "1") (pinfunction "1_1") (pintype "passive"))
      (node (ref "FB4") (pin "2") (pinfunction "2_2") (pintype "passive"))
      (node (ref "R15") (pin "2") (pinfunction "2_2") (pintype "passive"))
      (node (ref "R16") (pin "2") (pinfunction "2_2") (pintype "passive"))
      (node (ref "R17") (pin "2") (pinfunction "2_2") (pintype "passive"))
      (node (ref "R18") (pin "2") (pinfunction "2_2") (pintype "passive"))
      (node (ref "R19") (pin "2") (pinfunction "2_2") (pintype "passive"))
      (node (ref "U1") (pin "64") (pinfunction "VDD33TXRX2_64") (pintype "passive"))
    )
    (net (code "58") (name "VDDCR") (class "Default")
      (node (ref "C11") (pin "2") (pinfunction "2_2") (pintype "passive"))
      (node (ref "C12") (pin "2") (pinfunction "2_2") (pintype "passive"))
      (node (ref "C13") (pin "2") (pinfunction "2_2") (pintype "passive"))
      (node (ref "C14") (pin "2") (pinfunction "2_2") (pintype "passive"))
      (node (ref "FB1") (pin "2") (pinfunction "2_2") (pintype "passive"))
      (node (ref "U1") (pin "24") (pinfunction "VDDCR_24") (pintype "passive"))
      (node (ref "U1") (pin "38") (pinfunction "VDDCR_38") (pintype "passive"))
      (node (ref "U1") (pin "6") (pinfunction "VDDCR_6") (pintype "passive"))
    )
    (net (code "59") (name "unconnected-(IN1-A1-Pad12)") (class "Default")
      (node (ref "IN1") (pin "12") (pinfunction "A1_12") (pintype "passive"))
    )
    (net (code "60") (name "unconnected-(IN1-C1-Pad11)") (class "Default")
      (node (ref "IN1") (pin "11") (pinfunction "C1_11") (pintype "passive"))
    )
    (net (code "61") (name "unconnected-(IN1-MTG-Pad15)") (class "Default")
      (node (ref "IN1") (pin "15") (pinfunction "MTG_15") (pintype "passive"))
    )
    (net (code "62") (name "unconnected-(IN1-MTG1-Pad16)") (class "Default")
      (node (ref "IN1") (pin "16") (pinfunction "MTG1_16") (pintype "passive"))
    )
    (net (code "63") (name "unconnected-(IN1-NC-Pad7)") (class "Default")
      (node (ref "IN1") (pin "7") (pinfunction "NC_7") (pintype "passive"))
    )
    (net (code "64") (name "unconnected-(OUT1-A1-Pad12)") (class "Default")
      (node (ref "OUT1") (pin "12") (pinfunction "A1_12") (pintype "passive"))
    )
    (net (code "65") (name "unconnected-(OUT1-C1-Pad11)") (class "Default")
      (node (ref "OUT1") (pin "11") (pinfunction "C1_11") (pintype "passive"))
    )
    (net (code "66") (name "unconnected-(OUT1-MTG-Pad15)") (class "Default")
      (node (ref "OUT1") (pin "15") (pinfunction "MTG_15") (pintype "passive"))
    )
    (net (code "67") (name "unconnected-(OUT1-MTG1-Pad16)") (class "Default")
      (node (ref "OUT1") (pin "16") (pinfunction "MTG1_16") (pintype "passive"))
    )
    (net (code "68") (name "unconnected-(OUT1-NC-Pad7)") (class "Default")
      (node (ref "OUT1") (pin "7") (pinfunction "NC_7") (pintype "passive"))
    )
    (net (code "69") (name "unconnected-(U1-OSCVDD12-Pad3)") (class "Default")
      (node (ref "U1") (pin "3") (pinfunction "OSCVDD12_3") (pintype "passive"))
    )
    (net (code "70") (name "unconnected-(Y1-OSC2-Pad2)") (class "Default")
      (node (ref "Y1") (pin "2") (pinfunction "OSC2_2") (pintype "passive"))
    )
    (net (code "71") (name "unconnected-(Y1-OSC2-Pad4)") (class "Default")
      (node (ref "Y1") (pin "4") (pinfunction "OSC2_4") (pintype "passive"))
    )
  )
)
